# diffprobe1channel.net
KiCad netlist of a schematic drawn in Altium Designer
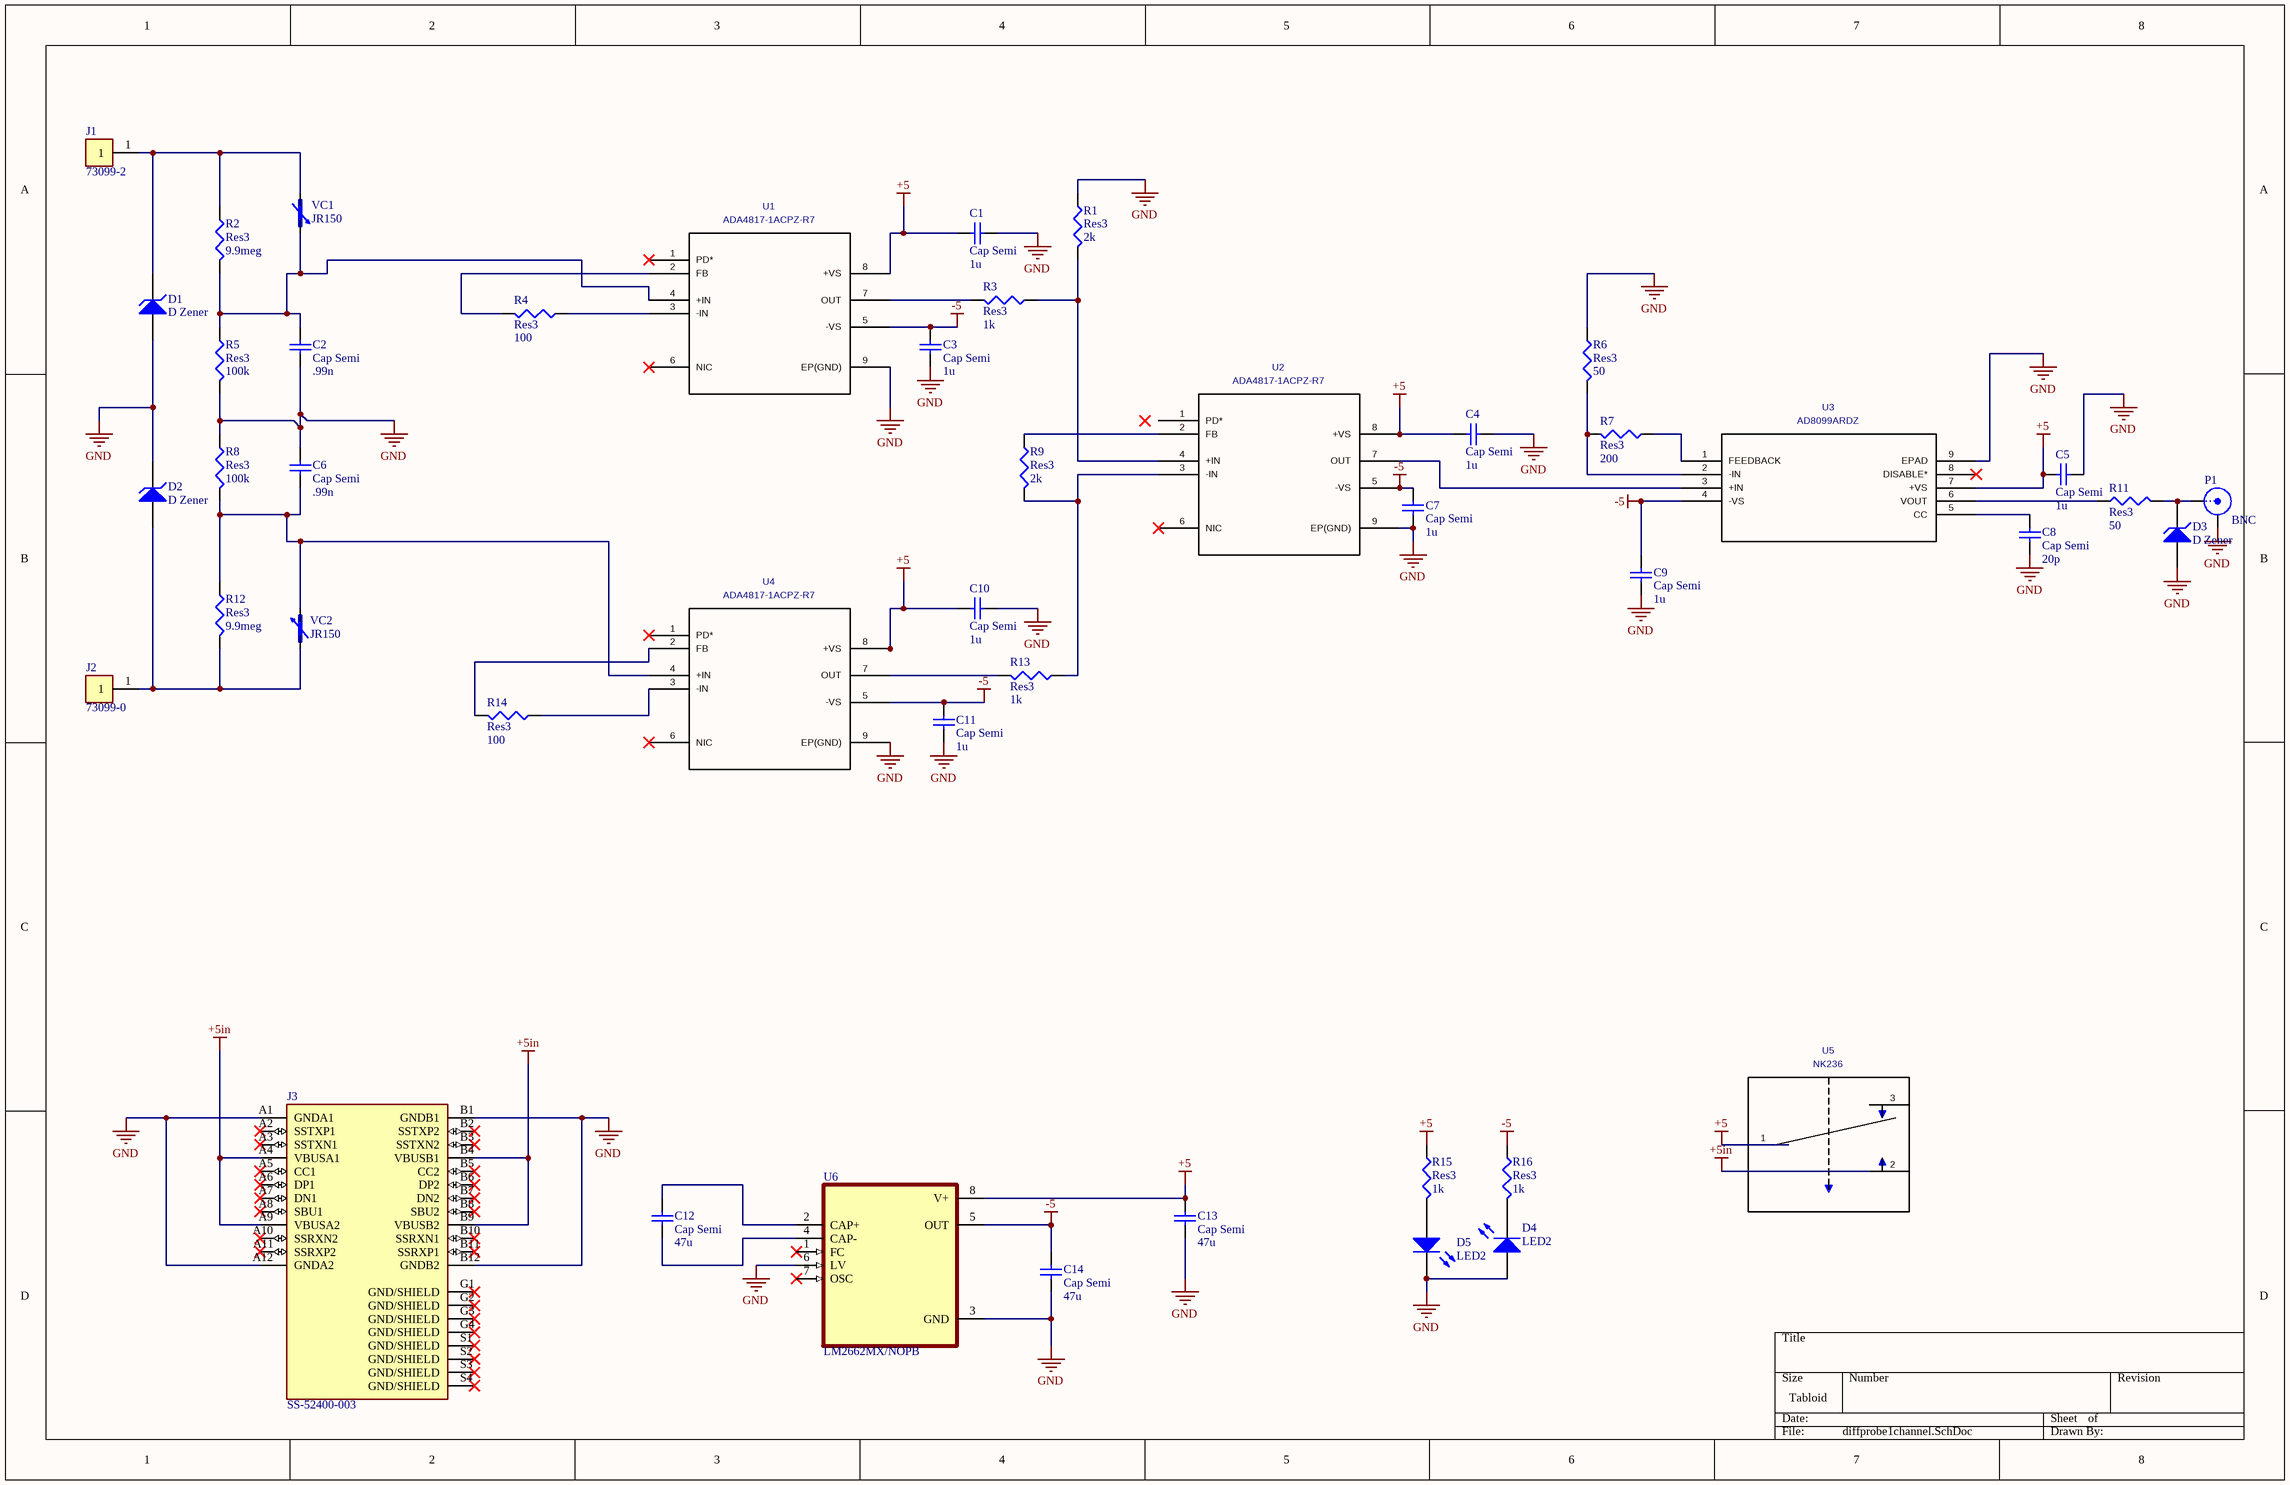
[diagram p0: diffprobe1channel.SchDoc]

(export (version "E")
  (design (tool "Eeschema 10.0.6"))
  (components
    (comp (ref "C1")
      (value "Cap Semi")
      (footprint "C0805")
      (description "Capacitor (Semiconductor SIM Model)")
      (fields (field (name "ALTIUM_VALUE") "1u") (field (name "PUBLISHER") "Altium Limited"))
      (libsource (lib "Miscellaneous Devices") (part "Cap Semi"))
    )
    (comp (ref "C2")
      (value "Cap Semi")
      (footprint "C0805")
      (description "Capacitor (Semiconductor SIM Model)")
      (fields (field (name "ALTIUM_VALUE") ".99n") (field (name "PUBLISHER") "Altium Limited"))
      (libsource (lib "Miscellaneous Devices") (part "Cap Semi"))
    )
    (comp (ref "C3")
      (value "Cap Semi")
      (footprint "C0805")
      (description "Capacitor (Semiconductor SIM Model)")
      (fields (field (name "ALTIUM_VALUE") "1u") (field (name "PUBLISHER") "Altium Limited"))
      (libsource (lib "Miscellaneous Devices") (part "Cap Semi"))
    )
    (comp (ref "C4")
      (value "Cap Semi")
      (footprint "C0805")
      (description "Capacitor (Semiconductor SIM Model)")
      (fields (field (name "ALTIUM_VALUE") "1u") (field (name "PUBLISHER") "Altium Limited"))
      (libsource (lib "Miscellaneous Devices") (part "Cap Semi"))
    )
    (comp (ref "C5")
      (value "Cap Semi")
      (footprint "C0805")
      (description "Capacitor (Semiconductor SIM Model)")
      (fields (field (name "ALTIUM_VALUE") "1u") (field (name "PUBLISHER") "Altium Limited"))
      (libsource (lib "Miscellaneous Devices") (part "Cap Semi"))
    )
    (comp (ref "C6")
      (value "Cap Semi")
      (footprint "C0805")
      (description "Capacitor (Semiconductor SIM Model)")
      (fields (field (name "ALTIUM_VALUE") ".99n") (field (name "PUBLISHER") "Altium Limited"))
      (libsource (lib "Miscellaneous Devices") (part "Cap Semi"))
    )
    (comp (ref "C7")
      (value "Cap Semi")
      (footprint "C0805")
      (description "Capacitor (Semiconductor SIM Model)")
      (fields (field (name "ALTIUM_VALUE") "1u") (field (name "PUBLISHER") "Altium Limited"))
      (libsource (lib "Miscellaneous Devices") (part "Cap Semi"))
    )
    (comp (ref "C8")
      (value "Cap Semi")
      (footprint "C0805")
      (description "Capacitor (Semiconductor SIM Model)")
      (fields (field (name "ALTIUM_VALUE") "20p") (field (name "PUBLISHER") "Altium Limited"))
      (libsource (lib "Miscellaneous Devices") (part "Cap Semi"))
    )
    (comp (ref "C9")
      (value "Cap Semi")
      (footprint "C0805")
      (description "Capacitor (Semiconductor SIM Model)")
      (fields (field (name "ALTIUM_VALUE") "1u") (field (name "PUBLISHER") "Altium Limited"))
      (libsource (lib "Miscellaneous Devices") (part "Cap Semi"))
    )
    (comp (ref "C10")
      (value "Cap Semi")
      (footprint "C0805")
      (description "Capacitor (Semiconductor SIM Model)")
      (fields (field (name "ALTIUM_VALUE") "1u") (field (name "PUBLISHER") "Altium Limited"))
      (libsource (lib "Miscellaneous Devices") (part "Cap Semi"))
    )
    (comp (ref "C11")
      (value "Cap Semi")
      (footprint "C0805")
      (description "Capacitor (Semiconductor SIM Model)")
      (fields (field (name "ALTIUM_VALUE") "1u") (field (name "PUBLISHER") "Altium Limited"))
      (libsource (lib "Miscellaneous Devices") (part "Cap Semi"))
    )
    (comp (ref "C12")
      (value "Cap Semi")
      (footprint "C0805")
      (description "Capacitor (Semiconductor SIM Model)")
      (fields (field (name "ALTIUM_VALUE") "47u") (field (name "PUBLISHER") "Altium Limited"))
      (libsource (lib "Miscellaneous Devices") (part "Cap Semi"))
    )
    (comp (ref "C13")
      (value "Cap Semi")
      (footprint "C0805")
      (description "Capacitor (Semiconductor SIM Model)")
      (fields (field (name "ALTIUM_VALUE") "47u") (field (name "PUBLISHER") "Altium Limited"))
      (libsource (lib "Miscellaneous Devices") (part "Cap Semi"))
    )
    (comp (ref "C14")
      (value "Cap Semi")
      (footprint "C0805")
      (description "Capacitor (Semiconductor SIM Model)")
      (fields (field (name "ALTIUM_VALUE") "47u") (field (name "PUBLISHER") "Altium Limited"))
      (libsource (lib "Miscellaneous Devices") (part "Cap Semi"))
    )
    (comp (ref "D1")
      (value "D Zener")
      (footprint "SMB")
      (description "Zener Diode")
      (fields (field (name "PUBLISHER") "Altium Limited"))
      (libsource (lib "Miscellaneous Devices") (part "D Zener"))
    )
    (comp (ref "D2")
      (value "D Zener")
      (footprint "SMB")
      (description "Zener Diode")
      (fields (field (name "PUBLISHER") "Altium Limited"))
      (libsource (lib "Miscellaneous Devices") (part "D Zener"))
    )
    (comp (ref "D3")
      (value "D Zener")
      (footprint "SMB")
      (description "Zener Diode")
      (fields (field (name "PUBLISHER") "Altium Limited"))
      (libsource (lib "Miscellaneous Devices") (part "D Zener"))
    )
    (comp (ref "D4")
      (value "LED2")
      (footprint "3.2X1.6X1.1")
      (description "Typical RED, GREEN, YELLOW, AMBER GaAs LED")
      (fields (field (name "PUBLISHER") "Altium Limited"))
      (libsource (lib "Miscellaneous Devices") (part "LED2"))
    )
    (comp (ref "D5")
      (value "LED2")
      (footprint "3.2X1.6X1.1")
      (description "Typical RED, GREEN, YELLOW, AMBER GaAs LED")
      (fields (field (name "PUBLISHER") "Altium Limited"))
      (libsource (lib "Miscellaneous Devices") (part "LED2"))
    )
    (comp (ref "J1")
      (value "73099-2")
      (footprint "POMONA_73099-0")
      (description "Banana Jack Connector Standard Banana Solder Black")
      (fields (field (name "MP") "73099-0") (field (name "DIGI-KEY_PART_NUMBER") "501-73099-0-ND"))
      (libsource (lib "diffproblibrary") (part "73099-0"))
    )
    (comp (ref "J2")
      (value "73099-0")
      (footprint "POMONA_73099-0")
      (description "Banana Jack Connector Standard Banana Solder Black")
      (fields (field (name "DIGI-KEY_PART_NUMBER") "501-73099-0-ND") (field (name "MF") "Pomona Electronics"))
      (libsource (lib "diffproblibrary") (part "73099-0"))
    )
    (comp (ref "J3")
      (value "SS-52400-003")
      (footprint "BELFUSE_SS-52400-003")
      (description "USB Type-C Connector ¦ 1 Port ¦ Right Angle Receptacle ¦ Shielded ¦ 0.063[1.60mm]")
      (fields (field (name "MF") "Stewart Connector"))
      (libsource (lib "diffproblibrary") (part "SS-52400-003"))
    )
    (comp (ref "P1")
      (value "BNC")
      (footprint "BNC_RA CON")
      (description "BNC Elbow Connector")
      (fields (field (name "PUBLISHER") "Altium Limited"))
      (libsource (lib "Miscellaneous Connectors") (part "BNC"))
    )
    (comp (ref "R1")
      (value "Res3")
      (footprint "J1-0603")
      (description "Resistor")
      (fields (field (name "ALTIUM_VALUE") "2k") (field (name "PUBLISHER") "Altium Limited"))
      (libsource (lib "Miscellaneous Devices") (part "Res3"))
    )
    (comp (ref "R2")
      (value "Res3")
      (footprint "J1-0603")
      (description "Resistor")
      (fields (field (name "ALTIUM_VALUE") "9.9meg") (field (name "PUBLISHER") "Altium Limited"))
      (libsource (lib "Miscellaneous Devices") (part "Res3"))
    )
    (comp (ref "R3")
      (value "Res3")
      (footprint "J1-0603")
      (description "Resistor")
      (fields (field (name "ALTIUM_VALUE") "1k") (field (name "PUBLISHER") "Altium Limited"))
      (libsource (lib "Miscellaneous Devices") (part "Res3"))
    )
    (comp (ref "R4")
      (value "Res3")
      (footprint "J1-0603")
      (description "Resistor")
      (fields (field (name "ALTIUM_VALUE") "100") (field (name "PUBLISHER") "Altium Limited"))
      (libsource (lib "Miscellaneous Devices") (part "Res3"))
    )
    (comp (ref "R5")
      (value "Res3")
      (footprint "J1-0603")
      (description "Resistor")
      (fields (field (name "ALTIUM_VALUE") "100k") (field (name "PUBLISHER") "Altium Limited"))
      (libsource (lib "Miscellaneous Devices") (part "Res3"))
    )
    (comp (ref "R6")
      (value "Res3")
      (footprint "J1-0603")
      (description "Resistor")
      (fields (field (name "ALTIUM_VALUE") "50") (field (name "PUBLISHER") "Altium Limited"))
      (libsource (lib "Miscellaneous Devices") (part "Res3"))
    )
    (comp (ref "R7")
      (value "Res3")
      (footprint "J1-0603")
      (description "Resistor")
      (fields (field (name "ALTIUM_VALUE") "200") (field (name "PUBLISHER") "Altium Limited"))
      (libsource (lib "Miscellaneous Devices") (part "Res3"))
    )
    (comp (ref "R8")
      (value "Res3")
      (footprint "J1-0603")
      (description "Resistor")
      (fields (field (name "ALTIUM_VALUE") "100k") (field (name "PUBLISHER") "Altium Limited"))
      (libsource (lib "Miscellaneous Devices") (part "Res3"))
    )
    (comp (ref "R9")
      (value "Res3")
      (footprint "J1-0603")
      (description "Resistor")
      (fields (field (name "ALTIUM_VALUE") "2k") (field (name "PUBLISHER") "Altium Limited"))
      (libsource (lib "Miscellaneous Devices") (part "Res3"))
    )
    (comp (ref "R11")
      (value "Res3")
      (footprint "J1-0603")
      (description "Resistor")
      (fields (field (name "ALTIUM_VALUE") "50") (field (name "PUBLISHER") "Altium Limited"))
      (libsource (lib "Miscellaneous Devices") (part "Res3"))
    )
    (comp (ref "R12")
      (value "Res3")
      (footprint "J1-0603")
      (description "Resistor")
      (fields (field (name "ALTIUM_VALUE") "9.9meg") (field (name "PUBLISHER") "Altium Limited"))
      (libsource (lib "Miscellaneous Devices") (part "Res3"))
    )
    (comp (ref "R13")
      (value "Res3")
      (footprint "J1-0603")
      (description "Resistor")
      (fields (field (name "ALTIUM_VALUE") "1k") (field (name "PUBLISHER") "Altium Limited"))
      (libsource (lib "Miscellaneous Devices") (part "Res3"))
    )
    (comp (ref "R14")
      (value "Res3")
      (footprint "J1-0603")
      (description "Resistor")
      (fields (field (name "ALTIUM_VALUE") "100") (field (name "PUBLISHER") "Altium Limited"))
      (libsource (lib "Miscellaneous Devices") (part "Res3"))
    )
    (comp (ref "R15")
      (value "Res3")
      (footprint "J1-0603")
      (description "Resistor")
      (fields (field (name "ALTIUM_VALUE") "1k") (field (name "PUBLISHER") "Altium Limited"))
      (libsource (lib "Miscellaneous Devices") (part "Res3"))
    )
    (comp (ref "R16")
      (value "Res3")
      (footprint "J1-0603")
      (description "Resistor")
      (fields (field (name "ALTIUM_VALUE") "1k") (field (name "PUBLISHER") "Altium Limited"))
      (libsource (lib "Miscellaneous Devices") (part "Res3"))
    )
    (comp (ref "U1")
      (value "ADA4817-1ACPZ-R7")
      (footprint "CP_8_13_ADI")
      (fields (field (name "COPYRIGHT") "Copyright (C) 2021 Ultra Librarian. All rights reserved."))
      (libsource (lib "diffproblibrary") (part "ADA4817-1ACPZ-R7"))
    )
    (comp (ref "U2")
      (value "ADA4817-1ACPZ-R7")
      (footprint "CP_8_13_ADI")
      (fields (field (name "COPYRIGHT") "Copyright (C) 2021 Ultra Librarian. All rights reserved."))
      (libsource (lib "diffproblibrary") (part "ADA4817-1ACPZ-R7"))
    )
    (comp (ref "U3")
      (value "AD8099ARDZ")
      (footprint "RD_8_1_ADI-L")
      (fields (field (name "COPYRIGHT") "Copyright (C) 2021 Ultra Librarian. All rights reserved."))
      (libsource (lib "diffproblibrary") (part "AD8099ARDZ"))
    )
    (comp (ref "U4")
      (value "ADA4817-1ACPZ-R7")
      (footprint "CP_8_13_ADI")
      (fields (field (name "COPYRIGHT") "Copyright (C) 2021 Ultra Librarian. All rights reserved."))
      (libsource (lib "diffproblibrary") (part "ADA4817-1ACPZ-R7"))
    )
    (comp (ref "U5")
      (value "NK236")
      (footprint "SWITCH_NK236_APM_NK236(Primary)")
      (fields (field (name "COPYRIGHT") "Copyright (C) 2021 Ultra Librarian. All rights reserved."))
      (libsource (lib "diffproblibrary") (part "NK236"))
    )
    (comp (ref "U6")
      (value "LM2662MX/NOPB")
      (footprint "SOIC127P599X175-8N")
      (description "200mA switched capacitor voltage converter 8-SOIC -40 to 85")
      (fields
        (field (name "DIGI-KEY_PART_NUMBER") "LM2662MX/NOPBCT-ND")
        (field (name "MF") "Texas Instruments")
      )
      (libsource (lib "diffproblibrary") (part "LM2662MX/NOPB"))
    )
    (comp (ref "VC1")
      (value "JR150")
      (footprint "CAPV_JR150")
      (description "3 ~ 15pF Trimmer Capacitor 125V Top Surface Mount")
      (fields (field (name "MF") "Knowles Voltronics"))
      (libsource (lib "diffproblibrary") (part "JR150"))
    )
    (comp (ref "VC2")
      (value "JR150")
      (footprint "CAPV_JR150")
      (description "3 ~ 15pF Trimmer Capacitor 125V Top Surface Mount")
      (fields (field (name "MF") "Knowles Voltronics"))
      (libsource (lib "") (part "JR150_1"))
    )
  )
  (nets
    (net (code "1") (name "+5") (class "Default")
      (node (ref "C1") (pin "1") (pinfunction "1_1") (pintype "passive"))
      (node (ref "C10") (pin "1") (pinfunction "1_1") (pintype "passive"))
      (node (ref "C13") (pin "2") (pinfunction "2_2") (pintype "passive"))
      (node (ref "C4") (pin "1") (pinfunction "1_1") (pintype "passive"))
      (node (ref "C5") (pin "1") (pinfunction "1_1") (pintype "passive"))
      (node (ref "R15") (pin "1") (pinfunction "1_1") (pintype "passive"))
      (node (ref "U1") (pin "8") (pinfunction "+VS_8") (pintype "power_in"))
      (node (ref "U2") (pin "8") (pinfunction "+VS_8") (pintype "power_in"))
      (node (ref "U3") (pin "7") (pinfunction "+VS_7") (pintype "power_in"))
      (node (ref "U4") (pin "8") (pinfunction "+VS_8") (pintype "power_in"))
      (node (ref "U5") (pin "1") (pinfunction "1_1") (pintype "passive"))
      (node (ref "U6") (pin "8") (pinfunction "V+_8") (pintype "power_in"))
    )
    (net (code "2") (name "+5in") (class "Default")
      (node (ref "J3") (pin "A4") (pinfunction "VBUSA1_A4") (pintype "power_in"))
      (node (ref "J3") (pin "A9") (pinfunction "VBUSA2_A9") (pintype "power_in"))
      (node (ref "J3") (pin "B4") (pinfunction "VBUSB1_B4") (pintype "power_in"))
      (node (ref "J3") (pin "B9") (pinfunction "VBUSB2_B9") (pintype "power_in"))
      (node (ref "U5") (pin "2") (pinfunction "2_2") (pintype "passive"))
    )
    (net (code "3") (name "-5") (class "Default")
      (node (ref "C11") (pin "2") (pinfunction "2_2") (pintype "passive"))
      (node (ref "C14") (pin "2") (pinfunction "2_2") (pintype "passive"))
      (node (ref "C3") (pin "2") (pinfunction "2_2") (pintype "passive"))
      (node (ref "C7") (pin "2") (pinfunction "2_2") (pintype "passive"))
      (node (ref "C9") (pin "2") (pinfunction "2_2") (pintype "passive"))
      (node (ref "R16") (pin "1") (pinfunction "1_1") (pintype "passive"))
      (node (ref "U1") (pin "5") (pinfunction "-VS_5") (pintype "power_in"))
      (node (ref "U2") (pin "5") (pinfunction "-VS_5") (pintype "power_in"))
      (node (ref "U3") (pin "4") (pinfunction "-VS_4") (pintype "power_in"))
      (node (ref "U4") (pin "5") (pinfunction "-VS_5") (pintype "power_in"))
      (node (ref "U6") (pin "5") (pinfunction "OUT_5") (pintype "power_in"))
    )
    (net (code "4") (name "GND") (class "Default")
      (node (ref "C1") (pin "2") (pinfunction "2_2") (pintype "passive"))
      (node (ref "C10") (pin "2") (pinfunction "2_2") (pintype "passive"))
      (node (ref "C11") (pin "1") (pinfunction "1_1") (pintype "passive"))
      (node (ref "C13") (pin "1") (pinfunction "1_1") (pintype "passive"))
      (node (ref "C14") (pin "1") (pinfunction "1_1") (pintype "passive"))
      (node (ref "C2") (pin "1") (pinfunction "1_1") (pintype "passive"))
      (node (ref "C3") (pin "1") (pinfunction "1_1") (pintype "passive"))
      (node (ref "C4") (pin "2") (pinfunction "2_2") (pintype "passive"))
      (node (ref "C5") (pin "2") (pinfunction "2_2") (pintype "passive"))
      (node (ref "C6") (pin "2") (pinfunction "2_2") (pintype "passive"))
      (node (ref "C7") (pin "1") (pinfunction "1_1") (pintype "passive"))
      (node (ref "C8") (pin "2") (pinfunction "2_2") (pintype "passive"))
      (node (ref "C9") (pin "1") (pinfunction "1_1") (pintype "passive"))
      (node (ref "D1") (pin "1") (pinfunction "A_1") (pintype "passive"))
      (node (ref "D2") (pin "2") (pinfunction "K_2") (pintype "passive"))
      (node (ref "D3") (pin "1") (pinfunction "A_1") (pintype "passive"))
      (node (ref "D4") (pin "1") (pinfunction "A_1") (pintype "passive"))
      (node (ref "D5") (pin "2") (pinfunction "K_2") (pintype "passive"))
      (node (ref "J3") (pin "A1") (pinfunction "GNDA1_A1") (pintype "power_in"))
      (node (ref "J3") (pin "A12") (pinfunction "GNDA2_A12") (pintype "power_in"))
      (node (ref "J3") (pin "B1") (pinfunction "GNDB1_B1") (pintype "power_in"))
      (node (ref "J3") (pin "B12") (pinfunction "GNDB2_B12") (pintype "power_in"))
      (node (ref "P1") (pin "2") (pinfunction "Y_2") (pintype "passive"))
      (node (ref "R1") (pin "1") (pinfunction "1_1") (pintype "passive"))
      (node (ref "R5") (pin "2") (pinfunction "2_2") (pintype "passive"))
      (node (ref "R6") (pin "1") (pinfunction "1_1") (pintype "passive"))
      (node (ref "R8") (pin "1") (pinfunction "1_1") (pintype "passive"))
      (node (ref "U1") (pin "9") (pinfunction "EP(GND)_9") (pintype "passive"))
      (node (ref "U2") (pin "9") (pinfunction "EP(GND)_9") (pintype "passive"))
      (node (ref "U3") (pin "9") (pinfunction "EPAD_9") (pintype "passive"))
      (node (ref "U4") (pin "9") (pinfunction "EP(GND)_9") (pintype "passive"))
      (node (ref "U6") (pin "3") (pinfunction "GND_3") (pintype "power_in"))
      (node (ref "U6") (pin "6") (pinfunction "LV_6") (pintype "input"))
    )
    (net (code "5") (name "Net-(D1-K)") (class "Default")
      (node (ref "D1") (pin "2") (pinfunction "K_2") (pintype "passive"))
      (node (ref "J1") (pin "1") (pinfunction "1_1") (pintype "passive"))
      (node (ref "R2") (pin "1") (pinfunction "1_1") (pintype "passive"))
      (node (ref "VC1") (pin "1") (pinfunction "A_1") (pintype "passive"))
    )
    (net (code "6") (name "Net-(D2-A)") (class "Default")
      (node (ref "D2") (pin "1") (pinfunction "A_1") (pintype "passive"))
      (node (ref "J2") (pin "1") (pinfunction "1_1") (pintype "passive"))
      (node (ref "R12") (pin "2") (pinfunction "2_2") (pintype "passive"))
      (node (ref "VC2") (pin "1") (pinfunction "A_1") (pintype "passive"))
    )
    (net (code "7") (name "Net-(D3-K)") (class "Default")
      (node (ref "D3") (pin "2") (pinfunction "K_2") (pintype "passive"))
      (node (ref "P1") (pin "1") (pinfunction "X_1") (pintype "passive"))
      (node (ref "R11") (pin "2") (pinfunction "2_2") (pintype "passive"))
    )
    (net (code "8") (name "Net-(D4-K)") (class "Default")
      (node (ref "D4") (pin "2") (pinfunction "K_2") (pintype "passive"))
      (node (ref "R16") (pin "2") (pinfunction "2_2") (pintype "passive"))
    )
    (net (code "9") (name "Net-(D5-A)") (class "Default")
      (node (ref "D5") (pin "1") (pinfunction "A_1") (pintype "passive"))
      (node (ref "R15") (pin "2") (pinfunction "2_2") (pintype "passive"))
    )
    (net (code "10") (name "Net-(U1-+IN)") (class "Default")
      (node (ref "C2") (pin "2") (pinfunction "2_2") (pintype "passive"))
      (node (ref "R2") (pin "2") (pinfunction "2_2") (pintype "passive"))
      (node (ref "R5") (pin "1") (pinfunction "1_1") (pintype "passive"))
      (node (ref "U1") (pin "4") (pinfunction "+IN_4") (pintype "passive"))
      (node (ref "VC1") (pin "2") (pinfunction "E_2") (pintype "passive"))
    )
    (net (code "11") (name "Net-(U1--IN)") (class "Default")
      (node (ref "R4") (pin "1") (pinfunction "1_1") (pintype "passive"))
      (node (ref "U1") (pin "3") (pinfunction "-IN_3") (pintype "passive"))
    )
    (net (code "12") (name "Net-(U1-FB)") (class "Default")
      (node (ref "R4") (pin "2") (pinfunction "2_2") (pintype "passive"))
      (node (ref "U1") (pin "2") (pinfunction "FB_2") (pintype "passive"))
    )
    (net (code "13") (name "Net-(U1-OUT)") (class "Default")
      (node (ref "R3") (pin "2") (pinfunction "2_2") (pintype "passive"))
      (node (ref "U1") (pin "7") (pinfunction "OUT_7") (pintype "passive"))
    )
    (net (code "14") (name "Net-(U2-+IN)") (class "Default")
      (node (ref "R1") (pin "2") (pinfunction "2_2") (pintype "passive"))
      (node (ref "R3") (pin "1") (pinfunction "1_1") (pintype "passive"))
      (node (ref "U2") (pin "4") (pinfunction "+IN_4") (pintype "passive"))
    )
    (net (code "15") (name "Net-(U2--IN)") (class "Default")
      (node (ref "R13") (pin "1") (pinfunction "1_1") (pintype "passive"))
      (node (ref "R9") (pin "2") (pinfunction "2_2") (pintype "passive"))
      (node (ref "U2") (pin "3") (pinfunction "-IN_3") (pintype "passive"))
    )
    (net (code "16") (name "Net-(U2-FB)") (class "Default")
      (node (ref "R9") (pin "1") (pinfunction "1_1") (pintype "passive"))
      (node (ref "U2") (pin "2") (pinfunction "FB_2") (pintype "passive"))
    )
    (net (code "17") (name "Net-(U2-OUT)") (class "Default")
      (node (ref "U2") (pin "7") (pinfunction "OUT_7") (pintype "passive"))
      (node (ref "U3") (pin "3") (pinfunction "+IN_3") (pintype "passive"))
    )
    (net (code "18") (name "Net-(U3--IN)") (class "Default")
      (node (ref "R6") (pin "2") (pinfunction "2_2") (pintype "passive"))
      (node (ref "R7") (pin "2") (pinfunction "2_2") (pintype "passive"))
      (node (ref "U3") (pin "2") (pinfunction "-IN_2") (pintype "passive"))
    )
    (net (code "19") (name "Net-(U3-CC)") (class "Default")
      (node (ref "C8") (pin "1") (pinfunction "1_1") (pintype "passive"))
      (node (ref "U3") (pin "5") (pinfunction "CC_5") (pintype "passive"))
    )
    (net (code "20") (name "Net-(U3-FEEDBACK)") (class "Default")
      (node (ref "R7") (pin "1") (pinfunction "1_1") (pintype "passive"))
      (node (ref "U3") (pin "1") (pinfunction "FEEDBACK_1") (pintype "passive"))
    )
    (net (code "21") (name "Net-(U3-VOUT)") (class "Default")
      (node (ref "R11") (pin "1") (pinfunction "1_1") (pintype "passive"))
      (node (ref "U3") (pin "6") (pinfunction "VOUT_6") (pintype "passive"))
    )
    (net (code "22") (name "Net-(U4-+IN)") (class "Default")
      (node (ref "C6") (pin "1") (pinfunction "1_1") (pintype "passive"))
      (node (ref "R12") (pin "1") (pinfunction "1_1") (pintype "passive"))
      (node (ref "R8") (pin "2") (pinfunction "2_2") (pintype "passive"))
      (node (ref "U4") (pin "4") (pinfunction "+IN_4") (pintype "passive"))
      (node (ref "VC2") (pin "2") (pinfunction "E_2") (pintype "passive"))
    )
    (net (code "23") (name "Net-(U4--IN)") (class "Default")
      (node (ref "R14") (pin "1") (pinfunction "1_1") (pintype "passive"))
      (node (ref "U4") (pin "3") (pinfunction "-IN_3") (pintype "passive"))
    )
    (net (code "24") (name "Net-(U4-FB)") (class "Default")
      (node (ref "R14") (pin "2") (pinfunction "2_2") (pintype "passive"))
      (node (ref "U4") (pin "2") (pinfunction "FB_2") (pintype "passive"))
    )
    (net (code "25") (name "Net-(U4-OUT)") (class "Default")
      (node (ref "R13") (pin "2") (pinfunction "2_2") (pintype "passive"))
      (node (ref "U4") (pin "7") (pinfunction "OUT_7") (pintype "passive"))
    )
    (net (code "26") (name "Net-(U6-CAP+)") (class "Default")
      (node (ref "C12") (pin "2") (pinfunction "2_2") (pintype "passive"))
      (node (ref "U6") (pin "2") (pinfunction "CAP+_2") (pintype "power_in"))
    )
    (net (code "27") (name "Net-(U6-CAP-)") (class "Default")
      (node (ref "C12") (pin "1") (pinfunction "1_1") (pintype "passive"))
      (node (ref "U6") (pin "4") (pinfunction "CAP-_4") (pintype "power_in"))
    )
    (net (code "28") (name "unconnected-(J3-CC1-PadA5)") (class "Default")
      (node (ref "J3") (pin "A5") (pinfunction "CC1_A5") (pintype "bidirectional+no_connect"))
    )
    (net (code "29") (name "unconnected-(J3-CC2-PadB5)") (class "Default")
      (node (ref "J3") (pin "B5") (pinfunction "CC2_B5") (pintype "bidirectional+no_connect"))
    )
    (net (code "30") (name "unconnected-(J3-DN1-PadA7)") (class "Default")
      (node (ref "J3") (pin "A7") (pinfunction "DN1_A7") (pintype "bidirectional+no_connect"))
    )
    (net (code "31") (name "unconnected-(J3-DN2-PadB7)") (class "Default")
      (node (ref "J3") (pin "B7") (pinfunction "DN2_B7") (pintype "bidirectional+no_connect"))
    )
    (net (code "32") (name "unconnected-(J3-DP1-PadA6)") (class "Default")
      (node (ref "J3") (pin "A6") (pinfunction "DP1_A6") (pintype "bidirectional+no_connect"))
    )
    (net (code "33") (name "unconnected-(J3-DP2-PadB6)") (class "Default")
      (node (ref "J3") (pin "B6") (pinfunction "DP2_B6") (pintype "bidirectional+no_connect"))
    )
    (net (code "34") (name "unconnected-(J3-GND{slash}SHIELD-PadG1)") (class "Default")
      (node (ref "J3") (pin "G1") (pinfunction "GND/SHIELD_G1") (pintype "power_in+no_connect"))
    )
    (net (code "35") (name "unconnected-(J3-GND{slash}SHIELD-PadG2)") (class "Default")
      (node (ref "J3") (pin "G2") (pinfunction "GND/SHIELD_G2") (pintype "power_in+no_connect"))
    )
    (net (code "36") (name "unconnected-(J3-GND{slash}SHIELD-PadG3)") (class "Default")
      (node (ref "J3") (pin "G3") (pinfunction "GND/SHIELD_G3") (pintype "power_in+no_connect"))
    )
    (net (code "37") (name "unconnected-(J3-GND{slash}SHIELD-PadG4)") (class "Default")
      (node (ref "J3") (pin "G4") (pinfunction "GND/SHIELD_G4") (pintype "power_in+no_connect"))
    )
    (net (code "38") (name "unconnected-(J3-GND{slash}SHIELD-PadS1)") (class "Default")
      (node (ref "J3") (pin "S1") (pinfunction "GND/SHIELD_S1") (pintype "power_in+no_connect"))
    )
    (net (code "39") (name "unconnected-(J3-GND{slash}SHIELD-PadS2)") (class "Default")
      (node (ref "J3") (pin "S2") (pinfunction "GND/SHIELD_S2") (pintype "power_in+no_connect"))
    )
    (net (code "40") (name "unconnected-(J3-GND{slash}SHIELD-PadS3)") (class "Default")
      (node (ref "J3") (pin "S3") (pinfunction "GND/SHIELD_S3") (pintype "power_in+no_connect"))
    )
    (net (code "41") (name "unconnected-(J3-GND{slash}SHIELD-PadS4)") (class "Default")
      (node (ref "J3") (pin "S4") (pinfunction "GND/SHIELD_S4") (pintype "power_in+no_connect"))
    )
    (net (code "42") (name "unconnected-(J3-SBU1-PadA8)") (class "Default")
      (node (ref "J3") (pin "A8") (pinfunction "SBU1_A8") (pintype "bidirectional+no_connect"))
    )
    (net (code "43") (name "unconnected-(J3-SBU2-PadB8)") (class "Default")
      (node (ref "J3") (pin "B8") (pinfunction "SBU2_B8") (pintype "bidirectional+no_connect"))
    )
    (net (code "44") (name "unconnected-(J3-SSRXN1-PadB10)") (class "Default")
      (node (ref "J3") (pin "B10") (pinfunction "SSRXN1_B10") (pintype "bidirectional+no_connect"))
    )
    (net (code "45") (name "unconnected-(J3-SSRXN2-PadA10)") (class "Default")
      (node (ref "J3") (pin "A10") (pinfunction "SSRXN2_A10") (pintype "bidirectional+no_connect"))
    )
    (net (code "46") (name "unconnected-(J3-SSRXP1-PadB11)") (class "Default")
      (node (ref "J3") (pin "B11") (pinfunction "SSRXP1_B11") (pintype "bidirectional+no_connect"))
    )
    (net (code "47") (name "unconnected-(J3-SSRXP2-PadA11)") (class "Default")
      (node (ref "J3") (pin "A11") (pinfunction "SSRXP2_A11") (pintype "bidirectional+no_connect"))
    )
    (net (code "48") (name "unconnected-(J3-SSTXN1-PadA3)") (class "Default")
      (node (ref "J3") (pin "A3") (pinfunction "SSTXN1_A3") (pintype "bidirectional+no_connect"))
    )
    (net (code "49") (name "unconnected-(J3-SSTXN2-PadB3)") (class "Default")
      (node (ref "J3") (pin "B3") (pinfunction "SSTXN2_B3") (pintype "bidirectional+no_connect"))
    )
    (net (code "50") (name "unconnected-(J3-SSTXP1-PadA2)") (class "Default")
      (node (ref "J3") (pin "A2") (pinfunction "SSTXP1_A2") (pintype "bidirectional+no_connect"))
    )
    (net (code "51") (name "unconnected-(J3-SSTXP2-PadB2)") (class "Default")
      (node (ref "J3") (pin "B2") (pinfunction "SSTXP2_B2") (pintype "bidirectional+no_connect"))
    )
    (net (code "52") (name "unconnected-(U1-NIC-Pad6)") (class "Default")
      (node (ref "U1") (pin "6") (pinfunction "NIC_6") (pintype "passive+no_connect"))
    )
    (net (code "53") (name "unconnected-(U1-PD*-Pad1)") (class "Default")
      (node (ref "U1") (pin "1") (pinfunction "PD*_1") (pintype "passive+no_connect"))
    )
    (net (code "54") (name "unconnected-(U2-NIC-Pad6)") (class "Default")
      (node (ref "U2") (pin "6") (pinfunction "NIC_6") (pintype "passive+no_connect"))
    )
    (net (code "55") (name "unconnected-(U2-PD*-Pad1)") (class "Default")
      (node (ref "U2") (pin "1") (pinfunction "PD*_1") (pintype "passive"))
    )
    (net (code "56") (name "unconnected-(U3-DISABLE*-Pad8)") (class "Default")
      (node (ref "U3") (pin "8") (pinfunction "DISABLE*_8") (pintype "passive+no_connect"))
    )
    (net (code "57") (name "unconnected-(U4-NIC-Pad6)") (class "Default")
      (node (ref "U4") (pin "6") (pinfunction "NIC_6") (pintype "passive+no_connect"))
    )
    (net (code "58") (name "unconnected-(U4-PD*-Pad1)") (class "Default")
      (node (ref "U4") (pin "1") (pinfunction "PD*_1") (pintype "passive+no_connect"))
    )
    (net (code "59") (name "unconnected-(U5-Pad3)") (class "Default")
      (node (ref "U5") (pin "3") (pinfunction "3_3") (pintype "passive"))
    )
    (net (code "60") (name "unconnected-(U6-FC-Pad1)") (class "Default")
      (node (ref "U6") (pin "1") (pinfunction "FC_1") (pintype "input+no_connect"))
    )
    (net (code "61") (name "unconnected-(U6-OSC-Pad7)") (class "Default")
      (node (ref "U6") (pin "7") (pinfunction "OSC_7") (pintype "input+no_connect"))
    )
  )
)
